# COMPARE.net
KiCad netlist of a schematic drawn in EAGLE
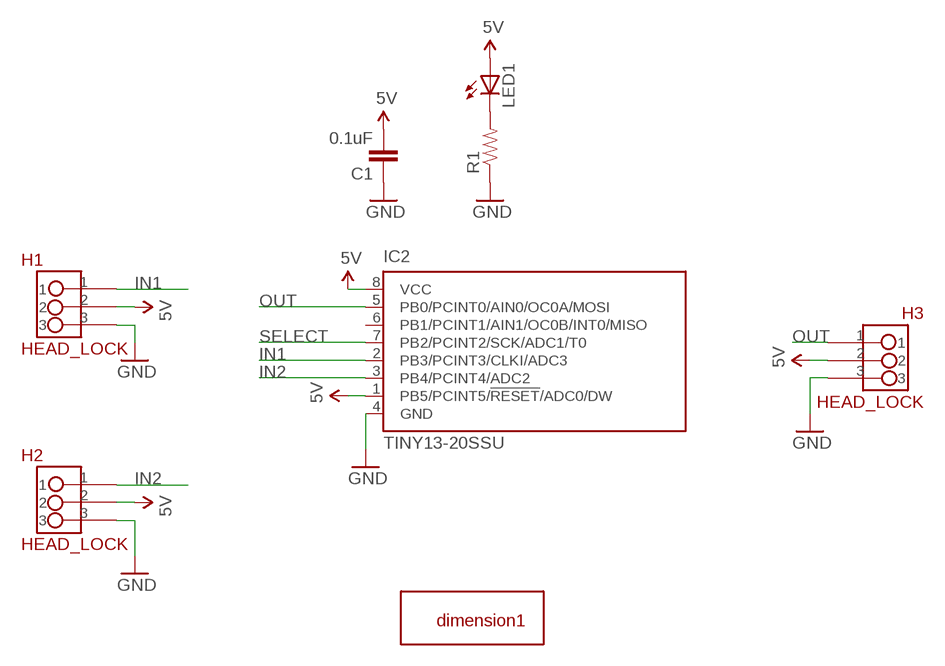
[diagram p0: schematic, sheet 1]

(export (version "E")
  (design (tool "Eeschema 10.0.6"))
  (components
    (comp (ref "C1")
      (value "0.1uF")
      (footprint "eagle-import:0603-CAP")
      (libsource (lib "eagle-import") (part "0.1UF-25V(+80/-20%)(0603)"))
    )
    (comp (ref "H1")
      (value "HEAD_LOCK")
      (footprint "eagle-import:HEAD_LOCK")
      (libsource (lib "eagle-import") (part "HEAD_LOCK"))
    )
    (comp (ref "H2")
      (value "HEAD_LOCK")
      (footprint "eagle-import:HEAD_LOCK")
      (libsource (lib "eagle-import") (part "HEAD_LOCK"))
    )
    (comp (ref "H3")
      (value "HEAD_LOCK")
      (footprint "eagle-import:HEAD_LOCK")
      (libsource (lib "eagle-import") (part "HEAD_LOCK"))
    )
    (comp (ref "IC2")
      (value "TINY13-20SSU")
      (footprint "eagle-import:8S1")
      (fields (field (name "MPN") "ATTINY13-20SSU"))
      (libsource (lib "eagle-import") (part "TINY13SSU-20"))
    )
    (comp (ref "LED1")
      (value "LEDSML0603")
      (footprint "eagle-import:SML0603")
      (libsource (lib "eagle-import") (part "LEDSML0603"))
    )
    (comp (ref "R1")
      (value "RESISTOR0603-RES")
      (footprint "eagle-import:0603-RES")
      (libsource (lib "eagle-import") (part "RESISTOR0603-RES"))
    )
    (comp (ref "U$1")
      (value "DIMENSION1")
      (footprint "eagle-import:DIMENSION1")
      (libsource (lib "eagle-import") (part "DIMENSION1"))
    )
  )
  (nets
    (net (code "1") (name "/IN1") (class "Default")
      (node (ref "H1") (pin "1") (pinfunction "1_1") (pintype "passive"))
      (node (ref "IC2") (pin "2") (pinfunction "PB3/PCINT3/CLKI/ADC3_2") (pintype "bidirectional"))
    )
    (net (code "2") (name "/IN2") (class "Default")
      (node (ref "H2") (pin "1") (pinfunction "1_1") (pintype "passive"))
      (node (ref "IC2") (pin "3") (pinfunction "PB4/PCINT4/ADC2_3") (pintype "bidirectional"))
    )
    (net (code "3") (name "/OUT") (class "Default")
      (node (ref "H3") (pin "1") (pinfunction "1_1") (pintype "passive"))
      (node (ref "IC2") (pin "5") (pinfunction "PB0/PCINT0/AIN0/OC0A/MOSI_5") (pintype "bidirectional"))
    )
    (net (code "4") (name "/SELECT") (class "Default")
      (node (ref "IC2") (pin "7") (pinfunction "PB2/PCINT2/SCK/ADC1/T0_7") (pintype "bidirectional"))
    )
    (net (code "5") (name "5V") (class "Default")
      (node (ref "C1") (pin "2") (pinfunction "2_2") (pintype "passive"))
      (node (ref "H1") (pin "2") (pinfunction "2_2") (pintype "passive"))
      (node (ref "H2") (pin "2") (pinfunction "2_2") (pintype "passive"))
      (node (ref "H3") (pin "2") (pinfunction "2_2") (pintype "passive"))
      (node (ref "IC2") (pin "1") (pinfunction "PB5/PCINT5/~{RESET}/ADC0/DW_1") (pintype "bidirectional"))
      (node (ref "IC2") (pin "8") (pinfunction "VCC_8") (pintype "power_in"))
      (node (ref "LED1") (pin "A") (pinfunction "A_A") (pintype "passive"))
    )
    (net (code "6") (name "GND") (class "Default")
      (node (ref "C1") (pin "1") (pinfunction "1_1") (pintype "passive"))
      (node (ref "H1") (pin "3") (pinfunction "3_3") (pintype "passive"))
      (node (ref "H2") (pin "3") (pinfunction "3_3") (pintype "passive"))
      (node (ref "H3") (pin "3") (pinfunction "3_3") (pintype "passive"))
      (node (ref "IC2") (pin "4") (pinfunction "GND_4") (pintype "power_in"))
      (node (ref "R1") (pin "1") (pinfunction "1_1") (pintype "passive"))
    )
    (net (code "7") (name "Net-(LED1-PadC)") (class "Default")
      (node (ref "LED1") (pin "C") (pinfunction "C_C") (pintype "passive"))
      (node (ref "R1") (pin "2") (pinfunction "2_2") (pintype "passive"))
    )
    (net (code "8") (name "unconnected-(IC2-PB1{slash}PCINT1{slash}AIN1{slash}OC0B{slash}INT0{slash}MISO-Pad6)") (class "Default")
      (node (ref "IC2") (pin "6") (pinfunction "PB1/PCINT1/AIN1/OC0B/INT0/MISO_6") (pintype "bidirectional"))
    )
  )
)
